# front_pot_plate.net
KiCad netlist of a schematic drawn in Altium Designer
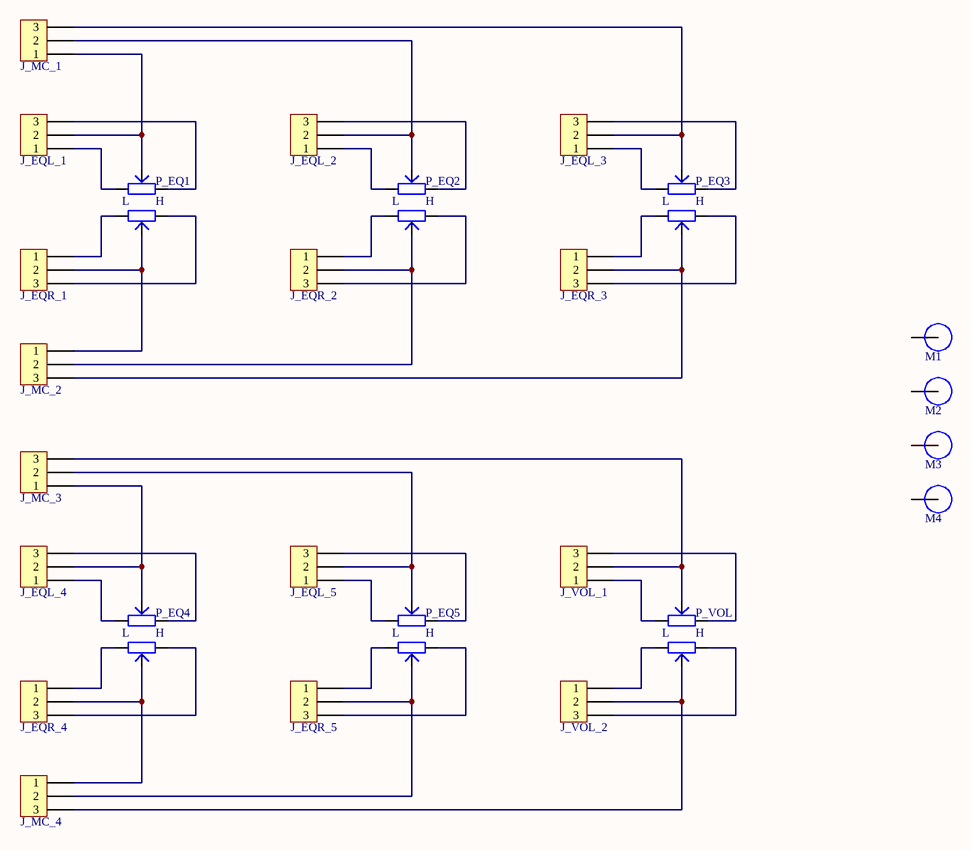
[diagram p0: front_pot_plate.SchDoc]

(export (version "E")
  (design (tool "Eeschema 10.0.6"))
  (components
    (comp (ref "J_EQL_1")
      (value "Header 1x3")
      (footprint "Header 1x3")
      (libsource (lib "") (part "Header 1x3_1"))
    )
    (comp (ref "J_EQL_2")
      (value "Header 1x3")
      (footprint "Header 1x3")
      (libsource (lib "") (part "Header 1x3_1"))
    )
    (comp (ref "J_EQL_3")
      (value "Header 1x3")
      (footprint "Header 1x3")
      (libsource (lib "") (part "Header 1x3_1"))
    )
    (comp (ref "J_EQL_4")
      (value "Header 1x3")
      (footprint "Header 1x3")
      (libsource (lib "") (part "Header 1x3_1"))
    )
    (comp (ref "J_EQL_5")
      (value "Header 1x3")
      (footprint "Header 1x3")
      (libsource (lib "") (part "Header 1x3_1"))
    )
    (comp (ref "J_EQR_1")
      (value "Header 1x3")
      (footprint "Header 1x3")
      (libsource (lib "AAURacing") (part "Header 1x3"))
    )
    (comp (ref "J_EQR_2")
      (value "Header 1x3")
      (footprint "Header 1x3")
      (libsource (lib "AAURacing") (part "Header 1x3"))
    )
    (comp (ref "J_EQR_3")
      (value "Header 1x3")
      (footprint "Header 1x3")
      (libsource (lib "AAURacing") (part "Header 1x3"))
    )
    (comp (ref "J_EQR_4")
      (value "Header 1x3")
      (footprint "Header 1x3")
      (libsource (lib "AAURacing") (part "Header 1x3"))
    )
    (comp (ref "J_EQR_5")
      (value "Header 1x3")
      (footprint "Header 1x3")
      (libsource (lib "AAURacing") (part "Header 1x3"))
    )
    (comp (ref "J_MC_1")
      (value "Header 1x3")
      (footprint "Header 1x3")
      (libsource (lib "") (part "Header 1x3_1"))
    )
    (comp (ref "J_MC_2")
      (value "Header 1x3")
      (footprint "Header 1x3")
      (libsource (lib "AAURacing") (part "Header 1x3"))
    )
    (comp (ref "J_MC_3")
      (value "Header 1x3")
      (footprint "Header 1x3")
      (libsource (lib "") (part "Header 1x3_1"))
    )
    (comp (ref "J_MC_4")
      (value "Header 1x3")
      (footprint "Header 1x3")
      (libsource (lib "AAURacing") (part "Header 1x3"))
    )
    (comp (ref "J_VOL_1")
      (value "Header 1x3")
      (footprint "Header 1x3")
      (libsource (lib "") (part "Header 1x3_1"))
    )
    (comp (ref "J_VOL_2")
      (value "Header 1x3")
      (footprint "Header 1x3")
      (libsource (lib "AAURacing") (part "Header 1x3"))
    )
    (comp (ref "M1")
      (value "Screw Hole")
      (footprint "M3 Hole")
      (libsource (lib "AAURacing") (part "Screw Hole"))
    )
    (comp (ref "M2")
      (value "Screw Hole")
      (footprint "M3 Hole")
      (libsource (lib "AAURacing") (part "Screw Hole"))
    )
    (comp (ref "M3")
      (value "Screw Hole")
      (footprint "M3 Hole")
      (libsource (lib "AAURacing") (part "Screw Hole"))
    )
    (comp (ref "M4")
      (value "Screw Hole")
      (footprint "M3 Hole")
      (libsource (lib "AAURacing") (part "Screw Hole"))
    )
    (comp (ref "P_EQ1")
      (value "stereo_pot")
      (footprint "POT STEREO LOOOOONG")
      (libsource (lib "esd410") (part "stereo_pot"))
    )
    (comp (ref "P_EQ2")
      (value "stereo_pot")
      (footprint "POT STEREO LOOOOONG")
      (libsource (lib "esd410") (part "stereo_pot"))
    )
    (comp (ref "P_EQ3")
      (value "stereo_pot")
      (footprint "POT STEREO LOOOOONG")
      (libsource (lib "esd410") (part "stereo_pot"))
    )
    (comp (ref "P_EQ4")
      (value "stereo_pot")
      (footprint "POT STEREO LOOOOONG")
      (libsource (lib "esd410") (part "stereo_pot"))
    )
    (comp (ref "P_EQ5")
      (value "stereo_pot")
      (footprint "POT STEREO LOOOOONG")
      (libsource (lib "esd410") (part "stereo_pot"))
    )
    (comp (ref "P_VOL")
      (value "stereo_pot")
      (footprint "POT STEREO LOOOOONG")
      (libsource (lib "esd410") (part "stereo_pot"))
    )
  )
  (nets
    (net (code "1") (name "Net-(J_EQL_1-Pad1)") (class "Default")
      (node (ref "J_EQL_1") (pin "1") (pinfunction "1_1") (pintype "passive"))
      (node (ref "P_EQ1") (pin "2") (pinfunction "2_2") (pintype "passive"))
    )
    (net (code "2") (name "Net-(J_EQL_1-Pad2)") (class "Default")
      (node (ref "J_EQL_1") (pin "2") (pinfunction "2_2") (pintype "passive"))
      (node (ref "J_MC_1") (pin "1") (pinfunction "1_1") (pintype "passive"))
      (node (ref "P_EQ1") (pin "3") (pinfunction "3_3") (pintype "passive"))
    )
    (net (code "3") (name "Net-(J_EQL_1-Pad3)") (class "Default")
      (node (ref "J_EQL_1") (pin "3") (pinfunction "3_3") (pintype "passive"))
      (node (ref "P_EQ1") (pin "1") (pinfunction "1_1") (pintype "passive"))
    )
    (net (code "4") (name "Net-(J_EQL_2-Pad1)") (class "Default")
      (node (ref "J_EQL_2") (pin "1") (pinfunction "1_1") (pintype "passive"))
      (node (ref "P_EQ2") (pin "2") (pinfunction "2_2") (pintype "passive"))
    )
    (net (code "5") (name "Net-(J_EQL_2-Pad2)") (class "Default")
      (node (ref "J_EQL_2") (pin "2") (pinfunction "2_2") (pintype "passive"))
      (node (ref "J_MC_1") (pin "2") (pinfunction "2_2") (pintype "passive"))
      (node (ref "P_EQ2") (pin "3") (pinfunction "3_3") (pintype "passive"))
    )
    (net (code "6") (name "Net-(J_EQL_2-Pad3)") (class "Default")
      (node (ref "J_EQL_2") (pin "3") (pinfunction "3_3") (pintype "passive"))
      (node (ref "P_EQ2") (pin "1") (pinfunction "1_1") (pintype "passive"))
    )
    (net (code "7") (name "Net-(J_EQL_3-Pad1)") (class "Default")
      (node (ref "J_EQL_3") (pin "1") (pinfunction "1_1") (pintype "passive"))
      (node (ref "P_EQ3") (pin "2") (pinfunction "2_2") (pintype "passive"))
    )
    (net (code "8") (name "Net-(J_EQL_3-Pad2)") (class "Default")
      (node (ref "J_EQL_3") (pin "2") (pinfunction "2_2") (pintype "passive"))
      (node (ref "J_MC_1") (pin "3") (pinfunction "3_3") (pintype "passive"))
      (node (ref "P_EQ3") (pin "3") (pinfunction "3_3") (pintype "passive"))
    )
    (net (code "9") (name "Net-(J_EQL_3-Pad3)") (class "Default")
      (node (ref "J_EQL_3") (pin "3") (pinfunction "3_3") (pintype "passive"))
      (node (ref "P_EQ3") (pin "1") (pinfunction "1_1") (pintype "passive"))
    )
    (net (code "10") (name "Net-(J_EQL_4-Pad1)") (class "Default")
      (node (ref "J_EQL_4") (pin "1") (pinfunction "1_1") (pintype "passive"))
      (node (ref "P_EQ4") (pin "2") (pinfunction "2_2") (pintype "passive"))
    )
    (net (code "11") (name "Net-(J_EQL_4-Pad2)") (class "Default")
      (node (ref "J_EQL_4") (pin "2") (pinfunction "2_2") (pintype "passive"))
      (node (ref "J_MC_3") (pin "1") (pinfunction "1_1") (pintype "passive"))
      (node (ref "P_EQ4") (pin "3") (pinfunction "3_3") (pintype "passive"))
    )
    (net (code "12") (name "Net-(J_EQL_4-Pad3)") (class "Default")
      (node (ref "J_EQL_4") (pin "3") (pinfunction "3_3") (pintype "passive"))
      (node (ref "P_EQ4") (pin "1") (pinfunction "1_1") (pintype "passive"))
    )
    (net (code "13") (name "Net-(J_EQL_5-Pad1)") (class "Default")
      (node (ref "J_EQL_5") (pin "1") (pinfunction "1_1") (pintype "passive"))
      (node (ref "P_EQ5") (pin "2") (pinfunction "2_2") (pintype "passive"))
    )
    (net (code "14") (name "Net-(J_EQL_5-Pad2)") (class "Default")
      (node (ref "J_EQL_5") (pin "2") (pinfunction "2_2") (pintype "passive"))
      (node (ref "J_MC_3") (pin "2") (pinfunction "2_2") (pintype "passive"))
      (node (ref "P_EQ5") (pin "3") (pinfunction "3_3") (pintype "passive"))
    )
    (net (code "15") (name "Net-(J_EQL_5-Pad3)") (class "Default")
      (node (ref "J_EQL_5") (pin "3") (pinfunction "3_3") (pintype "passive"))
      (node (ref "P_EQ5") (pin "1") (pinfunction "1_1") (pintype "passive"))
    )
    (net (code "16") (name "Net-(J_EQR_1-Pad1)") (class "Default")
      (node (ref "J_EQR_1") (pin "1") (pinfunction "1_1") (pintype "passive"))
      (node (ref "P_EQ1") (pin "5") (pinfunction "5_5") (pintype "passive"))
    )
    (net (code "17") (name "Net-(J_EQR_1-Pad2)") (class "Default")
      (node (ref "J_EQR_1") (pin "2") (pinfunction "2_2") (pintype "passive"))
      (node (ref "J_MC_2") (pin "1") (pinfunction "1_1") (pintype "passive"))
      (node (ref "P_EQ1") (pin "6") (pinfunction "6_6") (pintype "passive"))
    )
    (net (code "18") (name "Net-(J_EQR_1-Pad3)") (class "Default")
      (node (ref "J_EQR_1") (pin "3") (pinfunction "3_3") (pintype "passive"))
      (node (ref "P_EQ1") (pin "4") (pinfunction "4_4") (pintype "passive"))
    )
    (net (code "19") (name "Net-(J_EQR_2-Pad1)") (class "Default")
      (node (ref "J_EQR_2") (pin "1") (pinfunction "1_1") (pintype "passive"))
      (node (ref "P_EQ2") (pin "5") (pinfunction "5_5") (pintype "passive"))
    )
    (net (code "20") (name "Net-(J_EQR_2-Pad2)") (class "Default")
      (node (ref "J_EQR_2") (pin "2") (pinfunction "2_2") (pintype "passive"))
      (node (ref "J_MC_2") (pin "2") (pinfunction "2_2") (pintype "passive"))
      (node (ref "P_EQ2") (pin "6") (pinfunction "6_6") (pintype "passive"))
    )
    (net (code "21") (name "Net-(J_EQR_2-Pad3)") (class "Default")
      (node (ref "J_EQR_2") (pin "3") (pinfunction "3_3") (pintype "passive"))
      (node (ref "P_EQ2") (pin "4") (pinfunction "4_4") (pintype "passive"))
    )
    (net (code "22") (name "Net-(J_EQR_3-Pad1)") (class "Default")
      (node (ref "J_EQR_3") (pin "1") (pinfunction "1_1") (pintype "passive"))
      (node (ref "P_EQ3") (pin "5") (pinfunction "5_5") (pintype "passive"))
    )
    (net (code "23") (name "Net-(J_EQR_3-Pad2)") (class "Default")
      (node (ref "J_EQR_3") (pin "2") (pinfunction "2_2") (pintype "passive"))
      (node (ref "J_MC_2") (pin "3") (pinfunction "3_3") (pintype "passive"))
      (node (ref "P_EQ3") (pin "6") (pinfunction "6_6") (pintype "passive"))
    )
    (net (code "24") (name "Net-(J_EQR_3-Pad3)") (class "Default")
      (node (ref "J_EQR_3") (pin "3") (pinfunction "3_3") (pintype "passive"))
      (node (ref "P_EQ3") (pin "4") (pinfunction "4_4") (pintype "passive"))
    )
    (net (code "25") (name "Net-(J_EQR_4-Pad1)") (class "Default")
      (node (ref "J_EQR_4") (pin "1") (pinfunction "1_1") (pintype "passive"))
      (node (ref "P_EQ4") (pin "5") (pinfunction "5_5") (pintype "passive"))
    )
    (net (code "26") (name "Net-(J_EQR_4-Pad2)") (class "Default")
      (node (ref "J_EQR_4") (pin "2") (pinfunction "2_2") (pintype "passive"))
      (node (ref "J_MC_4") (pin "1") (pinfunction "1_1") (pintype "passive"))
      (node (ref "P_EQ4") (pin "6") (pinfunction "6_6") (pintype "passive"))
    )
    (net (code "27") (name "Net-(J_EQR_4-Pad3)") (class "Default")
      (node (ref "J_EQR_4") (pin "3") (pinfunction "3_3") (pintype "passive"))
      (node (ref "P_EQ4") (pin "4") (pinfunction "4_4") (pintype "passive"))
    )
    (net (code "28") (name "Net-(J_EQR_5-Pad1)") (class "Default")
      (node (ref "J_EQR_5") (pin "1") (pinfunction "1_1") (pintype "passive"))
      (node (ref "P_EQ5") (pin "5") (pinfunction "5_5") (pintype "passive"))
    )
    (net (code "29") (name "Net-(J_EQR_5-Pad2)") (class "Default")
      (node (ref "J_EQR_5") (pin "2") (pinfunction "2_2") (pintype "passive"))
      (node (ref "J_MC_4") (pin "2") (pinfunction "2_2") (pintype "passive"))
      (node (ref "P_EQ5") (pin "6") (pinfunction "6_6") (pintype "passive"))
    )
    (net (code "30") (name "Net-(J_EQR_5-Pad3)") (class "Default")
      (node (ref "J_EQR_5") (pin "3") (pinfunction "3_3") (pintype "passive"))
      (node (ref "P_EQ5") (pin "4") (pinfunction "4_4") (pintype "passive"))
    )
    (net (code "31") (name "Net-(J_MC_3-Pad3)") (class "Default")
      (node (ref "J_MC_3") (pin "3") (pinfunction "3_3") (pintype "passive"))
      (node (ref "J_VOL_1") (pin "2") (pinfunction "2_2") (pintype "passive"))
      (node (ref "P_VOL") (pin "3") (pinfunction "3_3") (pintype "passive"))
    )
    (net (code "32") (name "Net-(J_MC_4-Pad3)") (class "Default")
      (node (ref "J_MC_4") (pin "3") (pinfunction "3_3") (pintype "passive"))
      (node (ref "J_VOL_2") (pin "2") (pinfunction "2_2") (pintype "passive"))
      (node (ref "P_VOL") (pin "6") (pinfunction "6_6") (pintype "passive"))
    )
    (net (code "33") (name "Net-(J_VOL_1-Pad1)") (class "Default")
      (node (ref "J_VOL_1") (pin "1") (pinfunction "1_1") (pintype "passive"))
      (node (ref "P_VOL") (pin "2") (pinfunction "2_2") (pintype "passive"))
    )
    (net (code "34") (name "Net-(J_VOL_1-Pad3)") (class "Default")
      (node (ref "J_VOL_1") (pin "3") (pinfunction "3_3") (pintype "passive"))
      (node (ref "P_VOL") (pin "1") (pinfunction "1_1") (pintype "passive"))
    )
    (net (code "35") (name "Net-(J_VOL_2-Pad1)") (class "Default")
      (node (ref "J_VOL_2") (pin "1") (pinfunction "1_1") (pintype "passive"))
      (node (ref "P_VOL") (pin "5") (pinfunction "5_5") (pintype "passive"))
    )
    (net (code "36") (name "Net-(J_VOL_2-Pad3)") (class "Default")
      (node (ref "J_VOL_2") (pin "3") (pinfunction "3_3") (pintype "passive"))
      (node (ref "P_VOL") (pin "4") (pinfunction "4_4") (pintype "passive"))
    )
    (net (code "37") (name "unconnected-(M1-Pad1)") (class "Default")
      (node (ref "M1") (pin "1") (pinfunction "1_1") (pintype "passive"))
    )
    (net (code "38") (name "unconnected-(M2-Pad1)") (class "Default")
      (node (ref "M2") (pin "1") (pinfunction "1_1") (pintype "passive"))
    )
    (net (code "39") (name "unconnected-(M3-Pad1)") (class "Default")
      (node (ref "M3") (pin "1") (pinfunction "1_1") (pintype "passive"))
    )
    (net (code "40") (name "unconnected-(M4-Pad1)") (class "Default")
      (node (ref "M4") (pin "1") (pinfunction "1_1") (pintype "passive"))
    )
  )
)
